# K210.net
KiCad netlist of a schematic drawn in Altium Designer
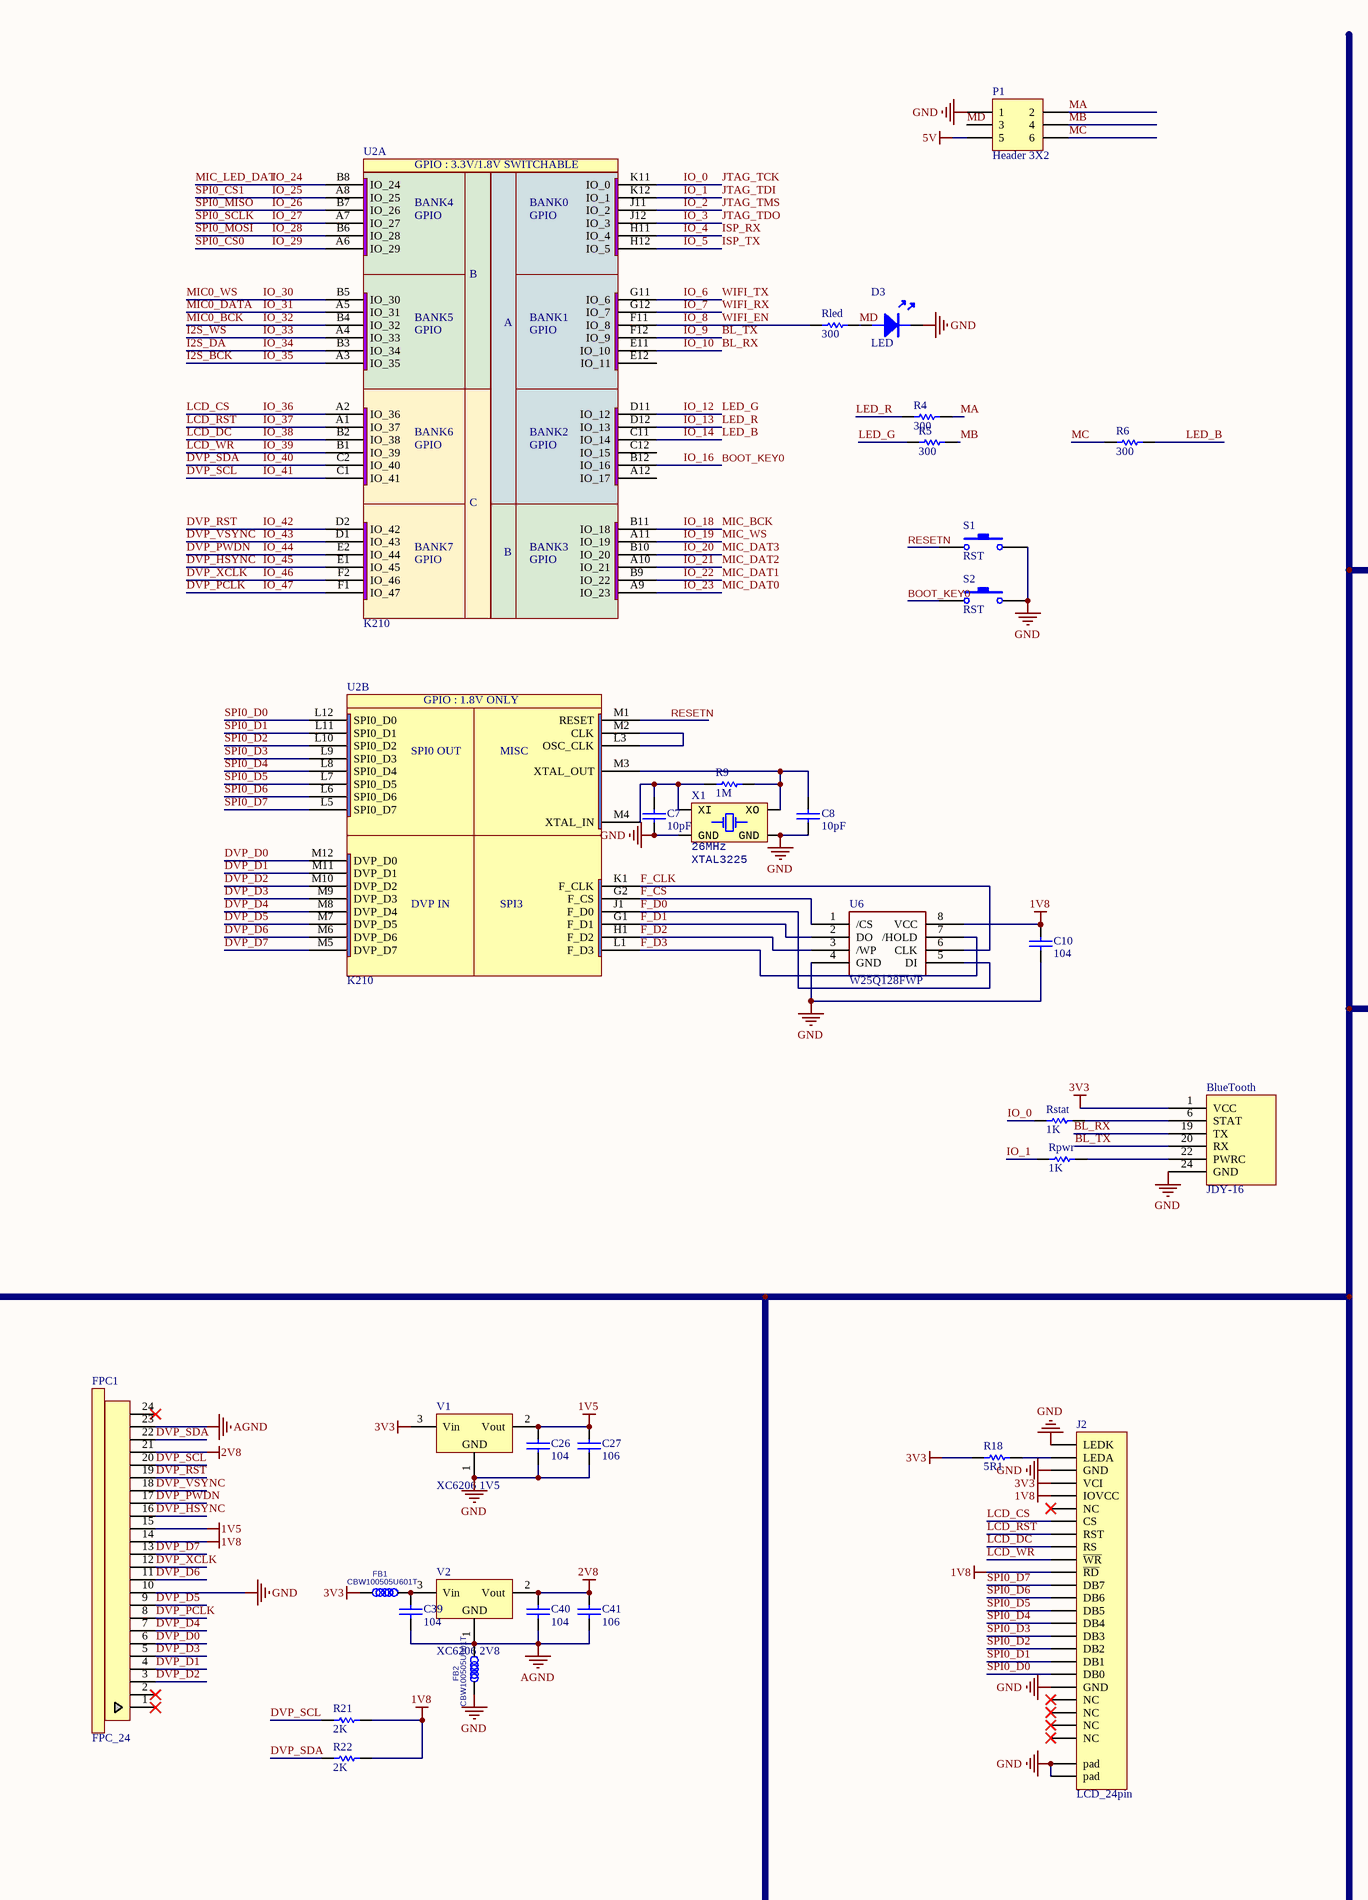
[diagram p0: K210.SchDoc, left]
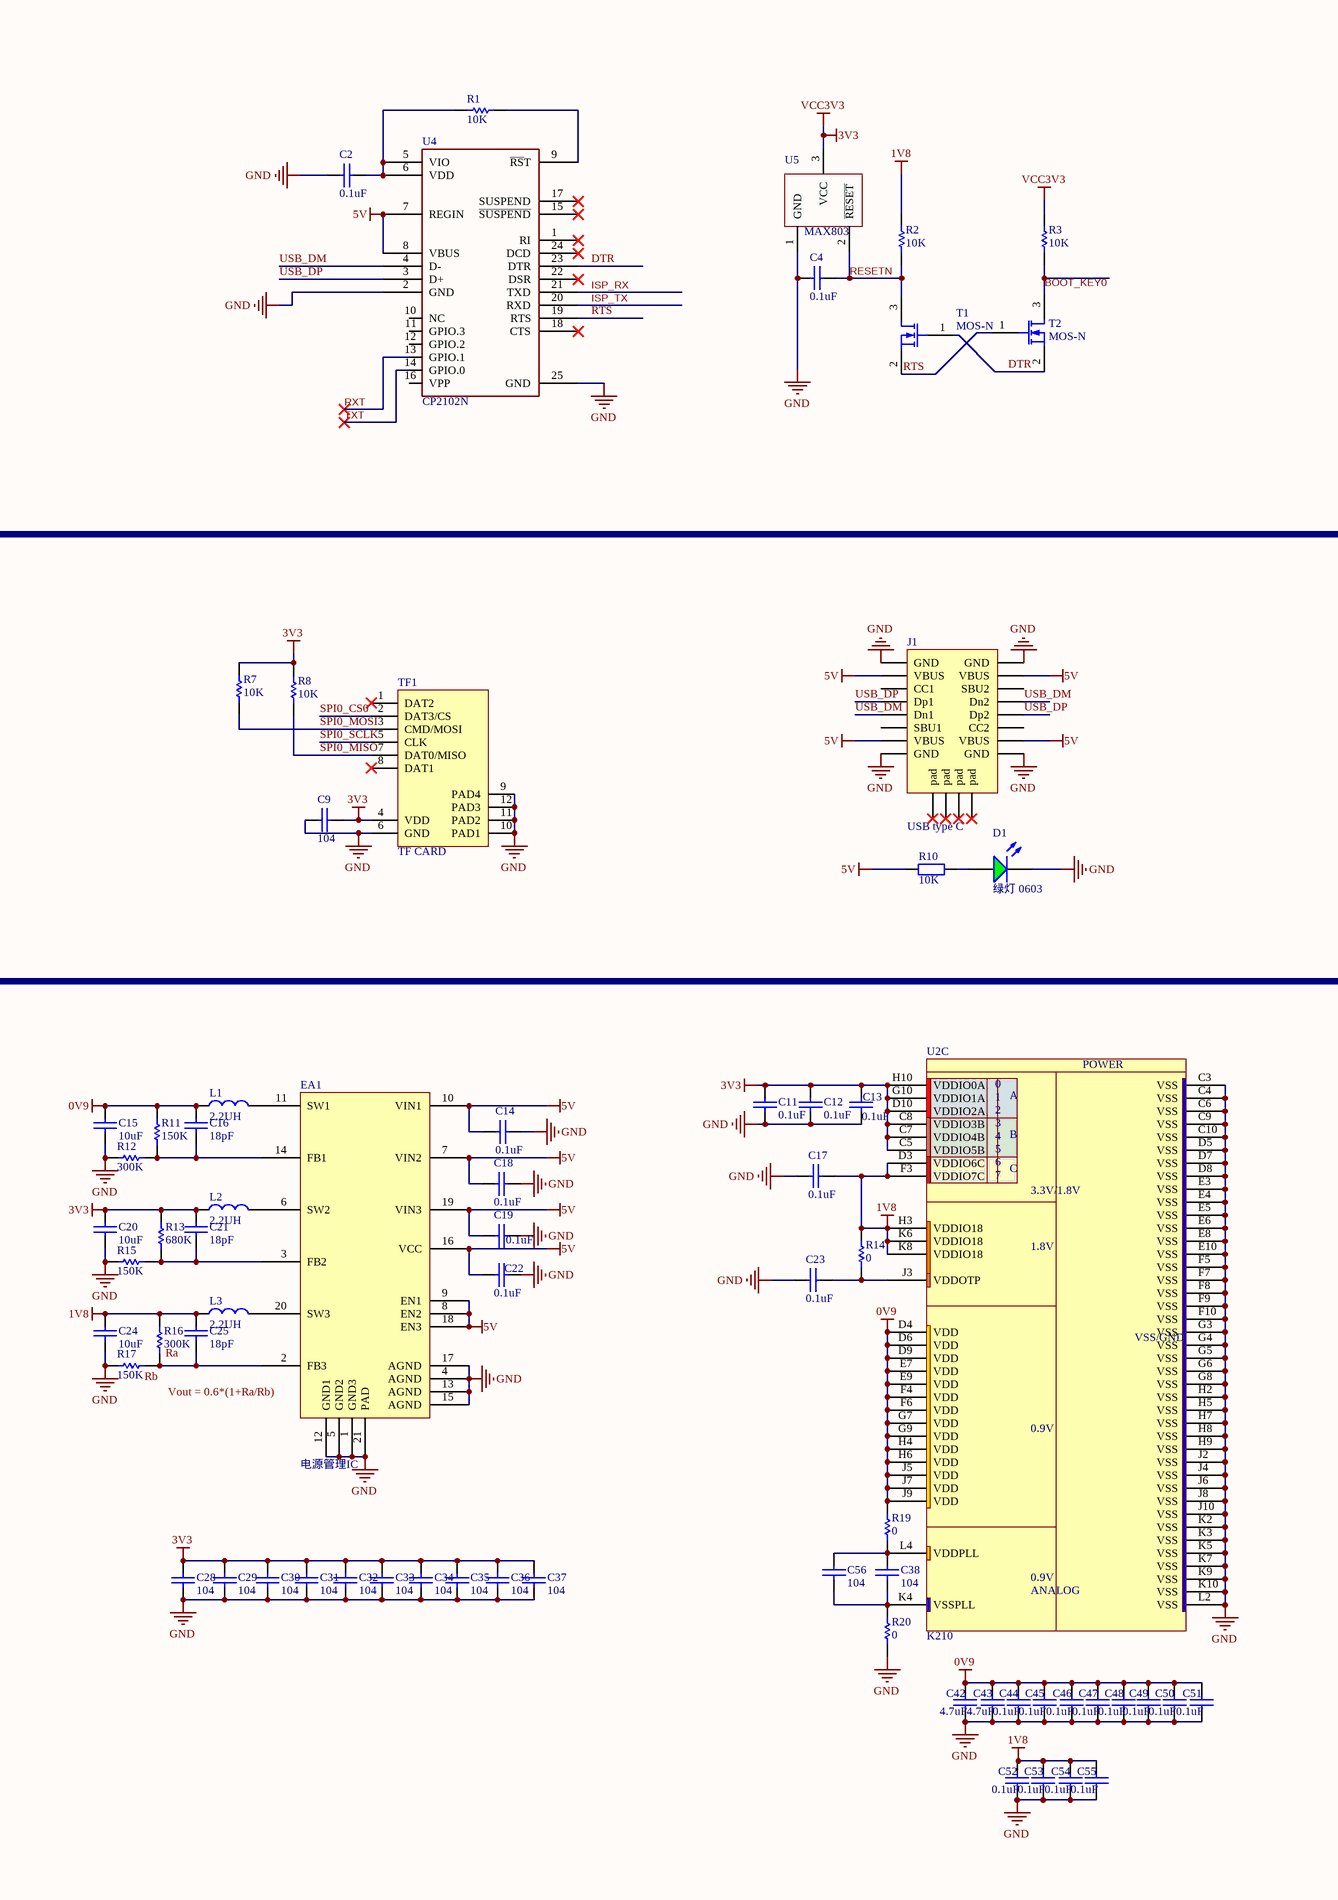
[diagram p1: K210.SchDoc, right]

(export (version "E")
  (design (tool "Eeschema 10.0.6"))
  (components
    (comp (ref "BlueTooth") (value "JDY-16") (footprint "JDY-16") (libsource (lib "未分类IC") (part "JDY-16")))
    (comp (ref "C2")
      (value "0.1uF")
      (footprint "0402C")
      (description "无极性电容")
      (libsource (lib "电容") (part "CAP"))
    )
    (comp (ref "C4")
      (value "0.1uF")
      (footprint "0402C")
      (description "无极性电容")
      (libsource (lib "电容") (part "CAP"))
    )
    (comp (ref "C7")
      (value "10pF")
      (footprint "0402C")
      (description "无极性电容")
      (libsource (lib "电容") (part "CAP"))
    )
    (comp (ref "C8")
      (value "10pF")
      (footprint "0402C")
      (description "无极性电容")
      (libsource (lib "电容") (part "CAP"))
    )
    (comp (ref "C9")
      (value "104")
      (footprint "0402C")
      (description "无极性电容")
      (libsource (lib "电容") (part "CAP"))
    )
    (comp (ref "C10")
      (value "104")
      (footprint "0402C")
      (description "无极性电容")
      (libsource (lib "电容") (part "CAP"))
    )
    (comp (ref "C11")
      (value "0.1uF")
      (footprint "0402C")
      (description "无极性电容")
      (libsource (lib "电容") (part "CAP"))
    )
    (comp (ref "C12")
      (value "0.1uF")
      (footprint "0402C")
      (description "无极性电容")
      (libsource (lib "电容") (part "CAP"))
    )
    (comp (ref "C13")
      (value "0.1uF")
      (footprint "0402C")
      (description "无极性电容")
      (libsource (lib "电容") (part "CAP"))
    )
    (comp (ref "C14")
      (value "0.1uF")
      (footprint "0402C")
      (description "无极性电容")
      (libsource (lib "电容") (part "CAP"))
    )
    (comp (ref "C15")
      (value "10uF")
      (footprint "0402C")
      (description "无极性电容")
      (libsource (lib "电容") (part "CAP"))
    )
    (comp (ref "C16")
      (value "18pF")
      (footprint "0402C")
      (description "无极性电容")
      (libsource (lib "电容") (part "CAP"))
    )
    (comp (ref "C17")
      (value "0.1uF")
      (footprint "0402C")
      (description "无极性电容")
      (libsource (lib "电容") (part "CAP"))
    )
    (comp (ref "C18")
      (value "0.1uF")
      (footprint "0402C")
      (description "无极性电容")
      (libsource (lib "电容") (part "CAP"))
    )
    (comp (ref "C19")
      (value "0.1uF")
      (footprint "0402C")
      (description "无极性电容")
      (libsource (lib "电容") (part "CAP"))
    )
    (comp (ref "C20")
      (value "10uF")
      (footprint "0402C")
      (description "无极性电容")
      (libsource (lib "电容") (part "CAP"))
    )
    (comp (ref "C21")
      (value "18pF")
      (footprint "0402C")
      (description "无极性电容")
      (libsource (lib "电容") (part "CAP"))
    )
    (comp (ref "C22")
      (value "0.1uF")
      (footprint "0402C")
      (description "无极性电容")
      (libsource (lib "电容") (part "CAP"))
    )
    (comp (ref "C23")
      (value "0.1uF")
      (footprint "0402C")
      (description "无极性电容")
      (libsource (lib "电容") (part "CAP"))
    )
    (comp (ref "C24")
      (value "10uF")
      (footprint "0402C")
      (description "无极性电容")
      (libsource (lib "电容") (part "CAP"))
    )
    (comp (ref "C25")
      (value "18pF")
      (footprint "0402C")
      (description "无极性电容")
      (libsource (lib "电容") (part "CAP"))
    )
    (comp (ref "C26")
      (value "104")
      (footprint "0402C")
      (description "无极性电容")
      (libsource (lib "电容") (part "CAP"))
    )
    (comp (ref "C27")
      (value "106")
      (footprint "0402C")
      (description "无极性电容")
      (libsource (lib "电容") (part "CAP"))
    )
    (comp (ref "C28")
      (value "104")
      (footprint "0402C")
      (description "无极性电容")
      (libsource (lib "电容") (part "CAP"))
    )
    (comp (ref "C29")
      (value "104")
      (footprint "0402C")
      (description "无极性电容")
      (libsource (lib "电容") (part "CAP"))
    )
    (comp (ref "C30")
      (value "104")
      (footprint "0402C")
      (description "无极性电容")
      (libsource (lib "电容") (part "CAP"))
    )
    (comp (ref "C31")
      (value "104")
      (footprint "0402C")
      (description "无极性电容")
      (libsource (lib "电容") (part "CAP"))
    )
    (comp (ref "C32")
      (value "104")
      (footprint "0402C")
      (description "无极性电容")
      (libsource (lib "电容") (part "CAP"))
    )
    (comp (ref "C33")
      (value "104")
      (footprint "0402C")
      (description "无极性电容")
      (libsource (lib "电容") (part "CAP"))
    )
    (comp (ref "C34")
      (value "104")
      (footprint "0402C")
      (description "无极性电容")
      (libsource (lib "电容") (part "CAP"))
    )
    (comp (ref "C35")
      (value "104")
      (footprint "0402C")
      (description "无极性电容")
      (libsource (lib "电容") (part "CAP"))
    )
    (comp (ref "C36")
      (value "104")
      (footprint "0402C")
      (description "无极性电容")
      (libsource (lib "电容") (part "CAP"))
    )
    (comp (ref "C37")
      (value "104")
      (footprint "0402C")
      (description "无极性电容")
      (libsource (lib "电容") (part "CAP"))
    )
    (comp (ref "C38")
      (value "104")
      (footprint "0402C")
      (description "无极性电容")
      (libsource (lib "电容") (part "CAP"))
    )
    (comp (ref "C39")
      (value "104")
      (footprint "0402C")
      (description "无极性电容")
      (libsource (lib "电容") (part "CAP"))
    )
    (comp (ref "C40")
      (value "104")
      (footprint "0402C")
      (description "无极性电容")
      (libsource (lib "电容") (part "CAP"))
    )
    (comp (ref "C41")
      (value "106")
      (footprint "0402C")
      (description "无极性电容")
      (libsource (lib "电容") (part "CAP"))
    )
    (comp (ref "C42")
      (value "4.7uF")
      (footprint "0402C")
      (description "无极性电容")
      (libsource (lib "电容") (part "CAP"))
    )
    (comp (ref "C43")
      (value "4.7uF")
      (footprint "0402C")
      (description "无极性电容")
      (libsource (lib "电容") (part "CAP"))
    )
    (comp (ref "C44")
      (value "0.1uF")
      (footprint "0402C")
      (description "无极性电容")
      (libsource (lib "电容") (part "CAP"))
    )
    (comp (ref "C45")
      (value "0.1uF")
      (footprint "0402C")
      (description "无极性电容")
      (libsource (lib "电容") (part "CAP"))
    )
    (comp (ref "C46")
      (value "0.1uF")
      (footprint "0402C")
      (description "无极性电容")
      (libsource (lib "电容") (part "CAP"))
    )
    (comp (ref "C47")
      (value "0.1uF")
      (footprint "0402C")
      (description "无极性电容")
      (libsource (lib "电容") (part "CAP"))
    )
    (comp (ref "C48")
      (value "0.1uF")
      (footprint "0402C")
      (description "无极性电容")
      (libsource (lib "电容") (part "CAP"))
    )
    (comp (ref "C49")
      (value "0.1uF")
      (footprint "0402C")
      (description "无极性电容")
      (libsource (lib "电容") (part "CAP"))
    )
    (comp (ref "C50")
      (value "0.1uF")
      (footprint "0402C")
      (description "无极性电容")
      (libsource (lib "电容") (part "CAP"))
    )
    (comp (ref "C51")
      (value "0.1uF")
      (footprint "0402C")
      (description "无极性电容")
      (libsource (lib "电容") (part "CAP"))
    )
    (comp (ref "C52")
      (value "0.1uF")
      (footprint "0402C")
      (description "无极性电容")
      (libsource (lib "电容") (part "CAP"))
    )
    (comp (ref "C53")
      (value "0.1uF")
      (footprint "0402C")
      (description "无极性电容")
      (libsource (lib "电容") (part "CAP"))
    )
    (comp (ref "C54")
      (value "0.1uF")
      (footprint "0402C")
      (description "无极性电容")
      (libsource (lib "电容") (part "CAP"))
    )
    (comp (ref "C55")
      (value "0.1uF")
      (footprint "0402C")
      (description "无极性电容")
      (libsource (lib "电容") (part "CAP"))
    )
    (comp (ref "C56")
      (value "104")
      (footprint "0402C")
      (description "无极性电容")
      (libsource (lib "电容") (part "CAP"))
    )
    (comp (ref "D1")
      (value "绿灯 0603")
      (footprint "0603_LED")
      (description "发光二极管")
      (libsource (lib "Miscellaneous Devices LC") (part "0603 绿灯"))
    )
    (comp (ref "D3") (value "LED") (footprint "LED-0603B") (libsource (lib "LED") (part "LED")))
    (comp (ref "EA1") (value "电源管理IC") (footprint "QFN20 3x3_M") (libsource (lib "XKZ") (part "EA3036")))
    (comp (ref "FB1") (value "CBW100505U601T") (footprint "0603_R") (libsource (lib "XKZ") (part "FB")))
    (comp (ref "FB2") (value "CBW100505U601T") (footprint "0603_R") (libsource (lib "XKZ") (part "FB")))
    (comp (ref "FPC1") (value "FPC_24") (footprint "FPC_24") (libsource (lib "XKZ") (part "FPC_24")))
    (comp (ref "J1")
      (value "USB type C")
      (footprint "USB Type-C-16Pin_A")
      (libsource (lib "XKZ") (part "USB_C"))
    )
    (comp (ref "J2") (value "LCD_24pin") (footprint "OV7740") (libsource (lib "XKZ") (part "LCD_24pin")))
    (comp (ref "L1")
      (value "2.2UH")
      (footprint "NR3015")
      (description "电感")
      (libsource (lib "XKZ") (part "L1"))
    )
    (comp (ref "L2")
      (value "2.2UH")
      (footprint "NR3015")
      (description "电感")
      (libsource (lib "XKZ") (part "L1"))
    )
    (comp (ref "L3")
      (value "2.2UH")
      (footprint "NR3015")
      (description "电感")
      (libsource (lib "XKZ") (part "L1"))
    )
    (comp (ref "P1")
      (value "Header 3X2")
      (footprint "HDR2X3")
      (description "Header, 3-Pin, Dual row")
      (fields (field (name "PUBLISHER") "Altium Limited"))
      (libsource (lib "Miscellaneous Connectors") (part "Header 3X2"))
    )
    (comp (ref "R1") (value "10K") (footprint "0402R") (libsource (lib "电阻") (part "RES")))
    (comp (ref "R2") (value "10K") (footprint "0402R") (libsource (lib "电阻") (part "RES")))
    (comp (ref "R3") (value "10K") (footprint "0402R") (libsource (lib "电阻") (part "RES")))
    (comp (ref "R4") (value "300") (footprint "0402R") (libsource (lib "电阻") (part "RES")))
    (comp (ref "R5") (value "300") (footprint "0402R") (libsource (lib "电阻") (part "RES")))
    (comp (ref "R6") (value "300") (footprint "0402R") (libsource (lib "电阻") (part "RES")))
    (comp (ref "R7") (value "10K") (footprint "0402R") (libsource (lib "电阻") (part "RES")))
    (comp (ref "R8") (value "10K") (footprint "0402R") (libsource (lib "电阻") (part "RES")))
    (comp (ref "R9") (value "1M") (footprint "0402R") (libsource (lib "电阻") (part "RES")))
    (comp (ref "R10")
      (value "10K")
      (footprint "0603_R")
      (description "Resistor")
      (fields (field (name "Comment") "Res2") (field (name "PUBLISHER") "Altium Limited"))
      (libsource (lib "XKZ") (part "Res2"))
    )
    (comp (ref "R11") (value "150K") (footprint "0402R") (libsource (lib "电阻") (part "RES")))
    (comp (ref "R12") (value "300K") (footprint "0402R") (libsource (lib "电阻") (part "RES")))
    (comp (ref "R13") (value "680K") (footprint "0402R") (libsource (lib "电阻") (part "RES")))
    (comp (ref "R14") (value "0") (footprint "0402R") (libsource (lib "电阻") (part "RES")))
    (comp (ref "R15") (value "150K") (footprint "0402R") (libsource (lib "电阻") (part "RES")))
    (comp (ref "R16") (value "300K") (footprint "0402R") (libsource (lib "电阻") (part "RES")))
    (comp (ref "R17") (value "150K") (footprint "0402R") (libsource (lib "电阻") (part "RES")))
    (comp (ref "R18") (value "5R1") (footprint "0402R") (libsource (lib "电阻") (part "RES")))
    (comp (ref "R19") (value "0") (footprint "0402R") (libsource (lib "电阻") (part "RES")))
    (comp (ref "R20") (value "0") (footprint "0402R") (libsource (lib "电阻") (part "RES")))
    (comp (ref "R21") (value "2K") (footprint "0402R") (libsource (lib "电阻") (part "RES")))
    (comp (ref "R22") (value "2K") (footprint "0402R") (libsource (lib "电阻") (part "RES")))
    (comp (ref "Rled") (value "300") (footprint "0402R") (libsource (lib "电阻") (part "RES")))
    (comp (ref "Rpwr") (value "1K") (footprint "0402R") (libsource (lib "电阻") (part "RES")))
    (comp (ref "Rstat") (value "1K") (footprint "0402R") (libsource (lib "电阻") (part "RES")))
    (comp (ref "S1")
      (value "RST")
      (footprint "KEY_1")
      (description "Switch")
      (fields (field (name "PUBLISHER") "Altium Limited"))
      (libsource (lib "自创 (1)") (part "SW-PB"))
    )
    (comp (ref "S2")
      (value "RST")
      (footprint "KEY_1")
      (description "Switch")
      (fields (field (name "PUBLISHER") "Altium Limited"))
      (libsource (lib "自创 (1)") (part "SW-PB"))
    )
    (comp (ref "T1") (value "MOS-N") (footprint "SOT23-3N") (libsource (lib "LIB_MANGO") (part "MOS-N")))
    (comp (ref "T2") (value "MOS-N") (footprint "SOT23-3N") (libsource (lib "LIB_MANGO") (part "MOS-N")))
    (comp (ref "TF1") (value "TF CARD") (footprint "TF卡座") (libsource (lib "XKZ") (part "SD_Card_flip")))
    (comp (ref "U2")
      (value "K210")
      (footprint "BGA144C65P12X12_800X800X95")
      (description "Canaan Kendryte K210 AI SoC")
      (libsource (lib "Vowstar_MCU") (part "K210"))
    )
    (comp (ref "U4")
      (value "CP2102N")
      (footprint "QFN24 4x4_N")
      (libsource (lib "LIB_MANGO") (part "CP2104"))
    )
    (comp (ref "U5") (value "MAX803") (footprint "SOT23-3N") (libsource (lib "LIB_MANGO") (part "MAX809")))
    (comp (ref "U6")
      (value "W25Q128FWP")
      (footprint "WSON8")
      (libsource (lib "LIB_MANGO") (part "SPIFLASH_SOP8W"))
    )
    (comp (ref "V1")
      (value "XC6206 1V5")
      (footprint "SOT23-3N")
      (description "低压差线性稳压芯片")
      (fields (field (name "版权归属") "源创客"))
      (libsource (lib "XKZ") (part "XC6206P332MR"))
    )
    (comp (ref "V2")
      (value "XC6206 2V8")
      (footprint "SOT23-3N")
      (description "低压差线性稳压芯片")
      (fields (field (name "版权归属") "源创客"))
      (libsource (lib "XKZ") (part "XC6206P332MR"))
    )
    (comp (ref "X1")
      (value "26MHz")
      (footprint "XT_3225_4")
      (description "Crystal Oscillator")
      (fields (field (name "TYPE") "XTAL3225"))
      (libsource (lib "XKZ") (part "XTAL_3225_4P"))
    )
  )
  (nets
    (net (code "1") (name "/BL_RX") (class "Default")
      (node (ref "BlueTooth") (pin "19") (pinfunction "TX_19") (pintype "passive"))
      (node (ref "U2") (pin "E11") (pinfunction "IO_10_E11") (pintype "passive"))
    )
    (net (code "2") (name "/BL_TX") (class "Default")
      (node (ref "BlueTooth") (pin "20") (pinfunction "RX_20") (pintype "passive"))
      (node (ref "U2") (pin "F12") (pinfunction "IO_9_F12") (pintype "passive"))
    )
    (net (code "3") (name "/BOOT_KEY0") (class "Default")
      (node (ref "R3") (pin "1") (pinfunction "1_1") (pintype "passive"))
      (node (ref "S2") (pin "1") (pinfunction "1_1") (pintype "passive"))
      (node (ref "T2") (pin "3") (pinfunction "3_3") (pintype "passive"))
      (node (ref "U2") (pin "B12") (pinfunction "IO_16_B12") (pintype "passive"))
    )
    (net (code "4") (name "/DTR") (class "Default")
      (node (ref "T1") (pin "1") (pinfunction "1_1") (pintype "passive"))
      (node (ref "T2") (pin "2") (pinfunction "2_2") (pintype "passive"))
      (node (ref "U4") (pin "23") (pinfunction "DTR_23") (pintype "passive"))
    )
    (net (code "5") (name "/DVP_D0") (class "Default")
      (node (ref "FPC1") (pin "6") (pinfunction "6_6") (pintype "passive"))
      (node (ref "U2") (pin "M12") (pinfunction "DVP_D0_M12") (pintype "passive"))
    )
    (net (code "6") (name "/DVP_D1") (class "Default")
      (node (ref "FPC1") (pin "4") (pinfunction "4_4") (pintype "passive"))
      (node (ref "U2") (pin "M11") (pinfunction "DVP_D1_M11") (pintype "passive"))
    )
    (net (code "7") (name "/DVP_D2") (class "Default")
      (node (ref "FPC1") (pin "3") (pinfunction "3_3") (pintype "passive"))
      (node (ref "U2") (pin "M10") (pinfunction "DVP_D2_M10") (pintype "passive"))
    )
    (net (code "8") (name "/DVP_D3") (class "Default")
      (node (ref "FPC1") (pin "5") (pinfunction "5_5") (pintype "passive"))
      (node (ref "U2") (pin "M9") (pinfunction "DVP_D3_M9") (pintype "passive"))
    )
    (net (code "9") (name "/DVP_D4") (class "Default")
      (node (ref "FPC1") (pin "7") (pinfunction "7_7") (pintype "passive"))
      (node (ref "U2") (pin "M8") (pinfunction "DVP_D4_M8") (pintype "passive"))
    )
    (net (code "10") (name "/DVP_D5") (class "Default")
      (node (ref "FPC1") (pin "9") (pinfunction "9_9") (pintype "passive"))
      (node (ref "U2") (pin "M7") (pinfunction "DVP_D5_M7") (pintype "passive"))
    )
    (net (code "11") (name "/DVP_D6") (class "Default")
      (node (ref "FPC1") (pin "11") (pinfunction "11_11") (pintype "passive"))
      (node (ref "U2") (pin "M6") (pinfunction "DVP_D6_M6") (pintype "passive"))
    )
    (net (code "12") (name "/DVP_D7") (class "Default")
      (node (ref "FPC1") (pin "13") (pinfunction "13_13") (pintype "passive"))
      (node (ref "U2") (pin "M5") (pinfunction "DVP_D7_M5") (pintype "passive"))
    )
    (net (code "13") (name "/DVP_HSYNC") (class "Default")
      (node (ref "FPC1") (pin "16") (pinfunction "16_16") (pintype "passive"))
      (node (ref "U2") (pin "E1") (pinfunction "IO_45_E1") (pintype "passive"))
    )
    (net (code "14") (name "/DVP_PCLK") (class "Default")
      (node (ref "FPC1") (pin "8") (pinfunction "8_8") (pintype "passive"))
      (node (ref "U2") (pin "F1") (pinfunction "IO_47_F1") (pintype "passive"))
    )
    (net (code "15") (name "/DVP_PWDN") (class "Default")
      (node (ref "FPC1") (pin "17") (pinfunction "17_17") (pintype "passive"))
      (node (ref "U2") (pin "E2") (pinfunction "IO_44_E2") (pintype "passive"))
    )
    (net (code "16") (name "/DVP_RST") (class "Default")
      (node (ref "FPC1") (pin "19") (pinfunction "19_19") (pintype "passive"))
      (node (ref "U2") (pin "D2") (pinfunction "IO_42_D2") (pintype "passive"))
    )
    (net (code "17") (name "/DVP_SCL") (class "Default")
      (node (ref "FPC1") (pin "20") (pinfunction "20_20") (pintype "passive"))
      (node (ref "R21") (pin "2") (pinfunction "2_2") (pintype "passive"))
      (node (ref "U2") (pin "C1") (pinfunction "IO_41_C1") (pintype "passive"))
    )
    (net (code "18") (name "/DVP_SDA") (class "Default")
      (node (ref "FPC1") (pin "22") (pinfunction "22_22") (pintype "passive"))
      (node (ref "R22") (pin "2") (pinfunction "2_2") (pintype "passive"))
      (node (ref "U2") (pin "C2") (pinfunction "IO_40_C2") (pintype "passive"))
    )
    (net (code "19") (name "/DVP_VSYNC") (class "Default")
      (node (ref "FPC1") (pin "18") (pinfunction "18_18") (pintype "passive"))
      (node (ref "U2") (pin "D1") (pinfunction "IO_43_D1") (pintype "passive"))
    )
    (net (code "20") (name "/DVP_XCLK") (class "Default")
      (node (ref "FPC1") (pin "12") (pinfunction "12_12") (pintype "passive"))
      (node (ref "U2") (pin "F2") (pinfunction "IO_46_F2") (pintype "passive"))
    )
    (net (code "21") (name "/F_CLK") (class "Default")
      (node (ref "U2") (pin "K1") (pinfunction "F_CLK_K1") (pintype "passive"))
      (node (ref "U6") (pin "6") (pinfunction "CLK_6") (pintype "passive"))
    )
    (net (code "22") (name "/F_CS") (class "Default")
      (node (ref "U2") (pin "G2") (pinfunction "F_CS_G2") (pintype "passive"))
      (node (ref "U6") (pin "1") (pinfunction "/CS_1") (pintype "passive"))
    )
    (net (code "23") (name "/F_D0") (class "Default")
      (node (ref "U2") (pin "J1") (pinfunction "F_D0_J1") (pintype "passive"))
      (node (ref "U6") (pin "5") (pinfunction "DI_5") (pintype "passive"))
    )
    (net (code "24") (name "/F_D1") (class "Default")
      (node (ref "U2") (pin "G1") (pinfunction "F_D1_G1") (pintype "passive"))
      (node (ref "U6") (pin "2") (pinfunction "DO_2") (pintype "passive"))
    )
    (net (code "25") (name "/F_D2") (class "Default")
      (node (ref "U2") (pin "H1") (pinfunction "F_D2_H1") (pintype "passive"))
      (node (ref "U6") (pin "3") (pinfunction "/WP_3") (pintype "passive"))
    )
    (net (code "26") (name "/F_D3") (class "Default")
      (node (ref "U2") (pin "L1") (pinfunction "F_D3_L1") (pintype "passive"))
      (node (ref "U6") (pin "7") (pinfunction "/HOLD_7") (pintype "passive"))
    )
    (net (code "27") (name "/I2S_BCK") (class "Default")
      (node (ref "U2") (pin "A3") (pinfunction "IO_35_A3") (pintype "passive"))
    )
    (net (code "28") (name "/I2S_DA") (class "Default")
      (node (ref "U2") (pin "B3") (pinfunction "IO_34_B3") (pintype "passive"))
    )
    (net (code "29") (name "/I2S_WS") (class "Default")
      (node (ref "U2") (pin "A4") (pinfunction "IO_33_A4") (pintype "passive"))
    )
    (net (code "30") (name "/IO_0") (class "Default")
      (node (ref "Rstat") (pin "2") (pinfunction "2_2") (pintype "passive"))
      (node (ref "U2") (pin "K11") (pinfunction "IO_0_K11") (pintype "passive"))
    )
    (net (code "31") (name "/IO_1") (class "Default")
      (node (ref "Rpwr") (pin "2") (pinfunction "2_2") (pintype "passive"))
      (node (ref "U2") (pin "K12") (pinfunction "IO_1_K12") (pintype "passive"))
    )
    (net (code "32") (name "/IO_2") (class "Default")
      (node (ref "U2") (pin "J11") (pinfunction "IO_2_J11") (pintype "passive"))
    )
    (net (code "33") (name "/IO_3") (class "Default")
      (node (ref "U2") (pin "J12") (pinfunction "IO_3_J12") (pintype "passive"))
    )
    (net (code "34") (name "/IO_4") (class "Default")
      (node (ref "U2") (pin "H11") (pinfunction "IO_4_H11") (pintype "passive"))
      (node (ref "U4") (pin "21") (pinfunction "TXD_21") (pintype "passive"))
    )
    (net (code "35") (name "/IO_5") (class "Default")
      (node (ref "U2") (pin "H12") (pinfunction "IO_5_H12") (pintype "passive"))
      (node (ref "U4") (pin "20") (pinfunction "RXD_20") (pintype "passive"))
    )
    (net (code "36") (name "/IO_6") (class "Default")
      (node (ref "U2") (pin "G11") (pinfunction "IO_6_G11") (pintype "passive"))
    )
    (net (code "37") (name "/IO_7") (class "Default")
      (node (ref "U2") (pin "G12") (pinfunction "IO_7_G12") (pintype "passive"))
    )
    (net (code "38") (name "/IO_8") (class "Default")
      (node (ref "Rled") (pin "2") (pinfunction "2_2") (pintype "passive"))
      (node (ref "U2") (pin "F11") (pinfunction "IO_8_F11") (pintype "passive"))
    )
    (net (code "39") (name "/IO_12") (class "Default")
      (node (ref "R5") (pin "2") (pinfunction "2_2") (pintype "passive"))
      (node (ref "U2") (pin "D11") (pinfunction "IO_12_D11") (pintype "passive"))
    )
    (net (code "40") (name "/IO_13") (class "Default")
      (node (ref "R4") (pin "2") (pinfunction "2_2") (pintype "passive"))
      (node (ref "U2") (pin "D12") (pinfunction "IO_13_D12") (pintype "passive"))
    )
    (net (code "41") (name "/IO_14") (class "Default")
      (node (ref "R6") (pin "1") (pinfunction "1_1") (pintype "passive"))
      (node (ref "U2") (pin "C11") (pinfunction "IO_14_C11") (pintype "passive"))
    )
    (net (code "42") (name "/IO_18") (class "Default")
      (node (ref "U2") (pin "B11") (pinfunction "IO_18_B11") (pintype "passive"))
    )
    (net (code "43") (name "/IO_19") (class "Default")
      (node (ref "U2") (pin "A11") (pinfunction "IO_19_A11") (pintype "passive"))
    )
    (net (code "44") (name "/IO_20") (class "Default")
      (node (ref "U2") (pin "B10") (pinfunction "IO_20_B10") (pintype "passive"))
    )
    (net (code "45") (name "/IO_21") (class "Default")
      (node (ref "U2") (pin "A10") (pinfunction "IO_21_A10") (pintype "passive"))
    )
    (net (code "46") (name "/IO_22") (class "Default")
      (node (ref "U2") (pin "B9") (pinfunction "IO_22_B9") (pintype "passive"))
    )
    (net (code "47") (name "/IO_23") (class "Default")
      (node (ref "U2") (pin "A9") (pinfunction "IO_23_A9") (pintype "passive"))
    )
    (net (code "48") (name "/IO_24") (class "Default")
      (node (ref "U2") (pin "B8") (pinfunction "IO_24_B8") (pintype "passive"))
    )
    (net (code "49") (name "/IO_25") (class "Default")
      (node (ref "U2") (pin "A8") (pinfunction "IO_25_A8") (pintype "passive"))
    )
    (net (code "50") (name "/IO_26") (class "Default")
      (node (ref "R8") (pin "1") (pinfunction "1_1") (pintype "passive"))
      (node (ref "TF1") (pin "7") (pinfunction "DAT0/MISO_7") (pintype "passive"))
      (node (ref "U2") (pin "B7") (pinfunction "IO_26_B7") (pintype "passive"))
    )
    (net (code "51") (name "/IO_27") (class "Default")
      (node (ref "TF1") (pin "5") (pinfunction "CLK_5") (pintype "passive"))
      (node (ref "U2") (pin "A7") (pinfunction "IO_27_A7") (pintype "passive"))
    )
    (net (code "52") (name "/IO_28") (class "Default")
      (node (ref "R7") (pin "1") (pinfunction "1_1") (pintype "passive"))
      (node (ref "TF1") (pin "3") (pinfunction "CMD/MOSI_3") (pintype "passive"))
      (node (ref "U2") (pin "B6") (pinfunction "IO_28_B6") (pintype "passive"))
    )
    (net (code "53") (name "/IO_29") (class "Default")
      (node (ref "TF1") (pin "2") (pinfunction "DAT3/CS_2") (pintype "passive"))
      (node (ref "U2") (pin "A6") (pinfunction "IO_29_A6") (pintype "passive"))
    )
    (net (code "54") (name "/IO_30") (class "Default")
      (node (ref "U2") (pin "B5") (pinfunction "IO_30_B5") (pintype "passive"))
    )
    (net (code "55") (name "/IO_31") (class "Default")
      (node (ref "U2") (pin "A5") (pinfunction "IO_31_A5") (pintype "passive"))
    )
    (net (code "56") (name "/IO_32") (class "Default")
      (node (ref "U2") (pin "B4") (pinfunction "IO_32_B4") (pintype "passive"))
    )
    (net (code "57") (name "/IO_36") (class "Default")
      (node (ref "J2") (pin "7") (pinfunction "CS_7") (pintype "passive"))
      (node (ref "U2") (pin "A2") (pinfunction "IO_36_A2") (pintype "passive"))
    )
    (net (code "58") (name "/IO_37") (class "Default")
      (node (ref "J2") (pin "8") (pinfunction "RST_8") (pintype "passive"))
      (node (ref "U2") (pin "A1") (pinfunction "IO_37_A1") (pintype "passive"))
    )
    (net (code "59") (name "/IO_38") (class "Default")
      (node (ref "J2") (pin "9") (pinfunction "RS_9") (pintype "passive"))
      (node (ref "U2") (pin "B2") (pinfunction "IO_38_B2") (pintype "passive"))
    )
    (net (code "60") (name "/IO_39") (class "Default")
      (node (ref "J2") (pin "10") (pinfunction "~{WR}_10") (pintype "passive"))
      (node (ref "U2") (pin "B1") (pinfunction "IO_39_B1") (pintype "passive"))
    )
    (net (code "61") (name "/MA") (class "Default")
      (node (ref "P1") (pin "2") (pinfunction "2_2") (pintype "passive"))
      (node (ref "R4") (pin "1") (pinfunction "1_1") (pintype "passive"))
    )
    (net (code "62") (name "/MB") (class "Default")
      (node (ref "P1") (pin "4") (pinfunction "4_4") (pintype "passive"))
      (node (ref "R5") (pin "1") (pinfunction "1_1") (pintype "passive"))
    )
    (net (code "63") (name "/MC") (class "Default")
      (node (ref "P1") (pin "6") (pinfunction "6_6") (pintype "passive"))
      (node (ref "R6") (pin "2") (pinfunction "2_2") (pintype "passive"))
    )
    (net (code "64") (name "/MD") (class "Default")
      (node (ref "D3") (pin "A") (pinfunction "A_A") (pintype "passive"))
      (node (ref "P1") (pin "3") (pinfunction "3_3") (pintype "passive"))
      (node (ref "Rled") (pin "1") (pinfunction "1_1") (pintype "passive"))
    )
    (net (code "65") (name "/RESETN") (class "Default")
      (node (ref "C4") (pin "2") (pinfunction "2_2") (pintype "passive"))
      (node (ref "R2") (pin "1") (pinfunction "1_1") (pintype "passive"))
      (node (ref "S1") (pin "1") (pinfunction "1_1") (pintype "passive"))
      (node (ref "T1") (pin "3") (pinfunction "3_3") (pintype "passive"))
      (node (ref "U2") (pin "M1") (pinfunction "RESET_M1") (pintype "passive"))
      (node (ref "U5") (pin "2") (pinfunction "~{RESET}_2") (pintype "passive"))
    )
    (net (code "66") (name "/RTS") (class "Default")
      (node (ref "T1") (pin "2") (pinfunction "2_2") (pintype "passive"))
      (node (ref "T2") (pin "1") (pinfunction "1_1") (pintype "passive"))
      (node (ref "U4") (pin "19") (pinfunction "RTS_19") (pintype "passive"))
    )
    (net (code "67") (name "/RXT") (class "Default")
      (node (ref "U4") (pin "13") (pinfunction "GPIO.1_13") (pintype "passive+no_connect"))
    )
    (net (code "70") (name "/SPI0_D0") (class "Default")
      (node (ref "J2") (pin "19") (pinfunction "DB0_19") (pintype "passive"))
      (node (ref "U2") (pin "L12") (pinfunction "SPI0_D0_L12") (pintype "passive"))
    )
    (net (code "71") (name "/SPI0_D1") (class "Default")
      (node (ref "J2") (pin "18") (pinfunction "DB1_18") (pintype "passive"))
      (node (ref "U2") (pin "L11") (pinfunction "SPI0_D1_L11") (pintype "passive"))
    )
    (net (code "72") (name "/SPI0_D2") (class "Default")
      (node (ref "J2") (pin "17") (pinfunction "DB2_17") (pintype "passive"))
      (node (ref "U2") (pin "L10") (pinfunction "SPI0_D2_L10") (pintype "passive"))
    )
    (net (code "73") (name "/SPI0_D3") (class "Default")
      (node (ref "J2") (pin "16") (pinfunction "DB3_16") (pintype "passive"))
      (node (ref "U2") (pin "L9") (pinfunction "SPI0_D3_L9") (pintype "passive"))
    )
    (net (code "74") (name "/SPI0_D4") (class "Default")
      (node (ref "J2") (pin "15") (pinfunction "DB4_15") (pintype "passive"))
      (node (ref "U2") (pin "L8") (pinfunction "SPI0_D4_L8") (pintype "passive"))
    )
    (net (code "75") (name "/SPI0_D5") (class "Default")
      (node (ref "J2") (pin "14") (pinfunction "DB5_14") (pintype "passive"))
      (node (ref "U2") (pin "L7") (pinfunction "SPI0_D5_L7") (pintype "passive"))
    )
    (net (code "76") (name "/SPI0_D6") (class "Default")
      (node (ref "J2") (pin "13") (pinfunction "DB6_13") (pintype "passive"))
      (node (ref "U2") (pin "L6") (pinfunction "SPI0_D6_L6") (pintype "passive"))
    )
    (net (code "77") (name "/SPI0_D7") (class "Default")
      (node (ref "J2") (pin "12") (pinfunction "DB7_12") (pintype "passive"))
      (node (ref "U2") (pin "L5") (pinfunction "SPI0_D7_L5") (pintype "passive"))
    )
    (net (code "78") (name "/TXT") (class "Default")
      (node (ref "U4") (pin "14") (pinfunction "GPIO.0_14") (pintype "passive+no_connect"))
    )
    (net (code "79") (name "/USB_DM") (class "Default")
      (node (ref "J1") (pin "A7") (pinfunction "Dn1_A7") (pintype "passive"))
      (node (ref "J1") (pin "B7") (pinfunction "Dn2_B7") (pintype "passive"))
      (node (ref "U4") (pin "4") (pinfunction "D-_4") (pintype "passive"))
    )
    (net (code "80") (name "/USB_DP") (class "Default")
      (node (ref "J1") (pin "A6") (pinfunction "Dp1_A6") (pintype "passive"))
      (node (ref "J1") (pin "B6") (pinfunction "Dp2_B6") (pintype "passive"))
      (node (ref "U4") (pin "3") (pinfunction "D+_3") (pintype "passive"))
    )
    (net (code "82") (name "0V9") (class "Default")
      (node (ref "C15") (pin "1") (pinfunction "1_1") (pintype "passive"))
      (node (ref "C16") (pin "1") (pinfunction "1_1") (pintype "passive"))
      (node (ref "C42") (pin "2") (pinfunction "2_2") (pintype "passive"))
      (node (ref "C43") (pin "2") (pinfunction "2_2") (pintype "passive"))
      (node (ref "C44") (pin "2") (pinfunction "2_2") (pintype "passive"))
      (node (ref "C45") (pin "2") (pinfunction "2_2") (pintype "passive"))
      (node (ref "C46") (pin "2") (pinfunction "2_2") (pintype "passive"))
      (node (ref "C47") (pin "2") (pinfunction "2_2") (pintype "passive"))
      (node (ref "C48") (pin "2") (pinfunction "2_2") (pintype "passive"))
      (node (ref "C49") (pin "2") (pinfunction "2_2") (pintype "passive"))
      (node (ref "C50") (pin "2") (pinfunction "2_2") (pintype "passive"))
      (node (ref "C51") (pin "2") (pinfunction "2_2") (pintype "passive"))
      (node (ref "L1") (pin "2") (pinfunction "2_2") (pintype "passive"))
      (node (ref "R11") (pin "2") (pinfunction "2_2") (pintype "passive"))
      (node (ref "R19") (pin "2") (pinfunction "2_2") (pintype "passive"))
      (node (ref "U2") (pin "D4") (pinfunction "VDD_D4") (pintype "power_in"))
      (node (ref "U2") (pin "D6") (pinfunction "VDD_D6") (pintype "power_in"))
      (node (ref "U2") (pin "D9") (pinfunction "VDD_D9") (pintype "power_in"))
      (node (ref "U2") (pin "E7") (pinfunction "VDD_E7") (pintype "power_in"))
      (node (ref "U2") (pin "E9") (pinfunction "VDD_E9") (pintype "power_in"))
      (node (ref "U2") (pin "F4") (pinfunction "VDD_F4") (pintype "power_in"))
      (node (ref "U2") (pin "F6") (pinfunction "VDD_F6") (pintype "power_in"))
      (node (ref "U2") (pin "G7") (pinfunction "VDD_G7") (pintype "power_in"))
      (node (ref "U2") (pin "G9") (pinfunction "VDD_G9") (pintype "power_in"))
      (node (ref "U2") (pin "H4") (pinfunction "VDD_H4") (pintype "power_in"))
      (node (ref "U2") (pin "H6") (pinfunction "VDD_H6") (pintype "power_in"))
      (node (ref "U2") (pin "J5") (pinfunction "VDD_J5") (pintype "power_in"))
      (node (ref "U2") (pin "J7") (pinfunction "VDD_J7") (pintype "power_in"))
      (node (ref "U2") (pin "J9") (pinfunction "VDD_J9") (pintype "power_in"))
    )
    (net (code "83") (name "1V5") (class "Default")
      (node (ref "C26") (pin "2") (pinfunction "2_2") (pintype "passive"))
      (node (ref "C27") (pin "2") (pinfunction "2_2") (pintype "passive"))
      (node (ref "FPC1") (pin "15") (pinfunction "15_15") (pintype "passive"))
      (node (ref "V1") (pin "2") (pinfunction "Vout_2") (pintype "passive"))
    )
    (net (code "84") (name "1V8") (class "Default")
      (node (ref "C10") (pin "2") (pinfunction "2_2") (pintype "passive"))
      (node (ref "C17") (pin "1") (pinfunction "1_1") (pintype "passive"))
      (node (ref "C24") (pin "1") (pinfunction "1_1") (pintype "passive"))
      (node (ref "C25") (pin "1") (pinfunction "1_1") (pintype "passive"))
      (node (ref "C52") (pin "2") (pinfunction "2_2") (pintype "passive"))
      (node (ref "C53") (pin "2") (pinfunction "2_2") (pintype "passive"))
      (node (ref "C54") (pin "2") (pinfunction "2_2") (pintype "passive"))
      (node (ref "C55") (pin "2") (pinfunction "2_2") (pintype "passive"))
      (node (ref "FPC1") (pin "14") (pinfunction "14_14") (pintype "passive"))
      (node (ref "J2") (pin "11") (pinfunction "~{RD}_11") (pintype "passive"))
      (node (ref "J2") (pin "5") (pinfunction "IOVCC_5") (pintype "passive"))
      (node (ref "L3") (pin "2") (pinfunction "2_2") (pintype "passive"))
      (node (ref "R14") (pin "2") (pinfunction "2_2") (pintype "passive"))
      (node (ref "R16") (pin "2") (pinfunction "2_2") (pintype "passive"))
      (node (ref "R2") (pin "2") (pinfunction "2_2") (pintype "passive"))
      (node (ref "R21") (pin "1") (pinfunction "1_1") (pintype "passive"))
      (node (ref "R22") (pin "1") (pinfunction "1_1") (pintype "passive"))
      (node (ref "U2") (pin "D3") (pinfunction "VDDIO6C_D3") (pintype "power_in"))
      (node (ref "U2") (pin "F3") (pinfunction "VDDIO7C_F3") (pintype "power_in"))
      (node (ref "U2") (pin "H3") (pinfunction "VDDIO18_H3") (pintype "power_in"))
      (node (ref "U2") (pin "K6") (pinfunction "VDDIO18_K6") (pintype "power_in"))
      (node (ref "U2") (pin "K8") (pinfunction "VDDIO18_K8") (pintype "power_in"))
      (node (ref "U6") (pin "8") (pinfunction "VCC_8") (pintype "passive"))
    )
    (net (code "85") (name "2V8") (class "Default")
      (node (ref "C40") (pin "2") (pinfunction "2_2") (pintype "passive"))
      (node (ref "C41") (pin "2") (pinfunction "2_2") (pintype "passive"))
      (node (ref "FPC1") (pin "21") (pinfunction "21_21") (pintype "passive"))
      (node (ref "V2") (pin "2") (pinfunction "Vout_2") (pintype "passive"))
    )
    (net (code "86") (name "3V3") (class "Default")
      (node (ref "BlueTooth") (pin "1") (pinfunction "VCC_1") (pintype "passive"))
      (node (ref "C11") (pin "1") (pinfunction "1_1") (pintype "passive"))
      (node (ref "C12") (pin "1") (pinfunction "1_1") (pintype "passive"))
      (node (ref "C13") (pin "1") (pinfunction "1_1") (pintype "passive"))
      (node (ref "C20") (pin "1") (pinfunction "1_1") (pintype "passive"))
      (node (ref "C21") (pin "1") (pinfunction "1_1") (pintype "passive"))
      (node (ref "C28") (pin "2") (pinfunction "2_2") (pintype "passive"))
      (node (ref "C29") (pin "2") (pinfunction "2_2") (pintype "passive"))
      (node (ref "C30") (pin "2") (pinfunction "2_2") (pintype "passive"))
      (node (ref "C31") (pin "2") (pinfunction "2_2") (pintype "passive"))
      (node (ref "C32") (pin "2") (pinfunction "2_2") (pintype "passive"))
      (node (ref "C33") (pin "2") (pinfunction "2_2") (pintype "passive"))
      (node (ref "C34") (pin "2") (pinfunction "2_2") (pintype "passive"))
      (node (ref "C35") (pin "2") (pinfunction "2_2") (pintype "passive"))
      (node (ref "C36") (pin "2") (pinfunction "2_2") (pintype "passive"))
      (node (ref "C37") (pin "2") (pinfunction "2_2") (pintype "passive"))
      (node (ref "C9") (pin "1") (pinfunction "1_1") (pintype "passive"))
      (node (ref "FB1") (pin "2") (pinfunction "2_2") (pintype "passive"))
      (node (ref "J2") (pin "4") (pinfunction "VCI_4") (pintype "passive"))
      (node (ref "L2") (pin "2") (pinfunction "2_2") (pintype "passive"))
      (node (ref "R13") (pin "2") (pinfunction "2_2") (pintype "passive"))
      (node (ref "R18") (pin "2") (pinfunction "2_2") (pintype "passive"))
      (node (ref "R3") (pin "2") (pinfunction "2_2") (pintype "passive"))
      (node (ref "R7") (pin "2") (pinfunction "2_2") (pintype "passive"))
      (node (ref "R8") (pin "2") (pinfunction "2_2") (pintype "passive"))
      (node (ref "TF1") (pin "4") (pinfunction "VDD_4") (pintype "passive"))
      (node (ref "U2") (pin "C5") (pinfunction "VDDIO5B_C5") (pintype "power_in"))
      (node (ref "U2") (pin "C7") (pinfunction "VDDIO4B_C7") (pintype "power_in"))
      (node (ref "U2") (pin "C8") (pinfunction "VDDIO3B_C8") (pintype "power_in"))
      (node (ref "U2") (pin "D10") (pinfunction "VDDIO2A_D10") (pintype "power_in"))
      (node (ref "U2") (pin "G10") (pinfunction "VDDIO1A_G10") (pintype "power_in"))
      (node (ref "U2") (pin "H10") (pinfunction "VDDIO0A_H10") (pintype "power_in"))
      (node (ref "U5") (pin "3") (pinfunction "VCC_3") (pintype "passive"))
      (node (ref "V1") (pin "3") (pinfunction "Vin_3") (pintype "passive"))
    )
    (net (code "87") (name "5V") (class "Default")
      (node (ref "C14") (pin "2") (pinfunction "2_2") (pintype "passive"))
      (node (ref "C18") (pin "2") (pinfunction "2_2") (pintype "passive"))
      (node (ref "C19") (pin "2") (pinfunction "2_2") (pintype "passive"))
      (node (ref "C22") (pin "2") (pinfunction "2_2") (pintype "passive"))
      (node (ref "EA1") (pin "10") (pinfunction "VIN1_10") (pintype "passive"))
      (node (ref "EA1") (pin "16") (pinfunction "VCC_16") (pintype "passive"))
      (node (ref "EA1") (pin "18") (pinfunction "EN3_18") (pintype "passive"))
      (node (ref "EA1") (pin "19") (pinfunction "VIN3_19") (pintype "passive"))
      (node (ref "EA1") (pin "7") (pinfunction "VIN2_7") (pintype "passive"))
      (node (ref "EA1") (pin "8") (pinfunction "EN2_8") (pintype "passive"))
      (node (ref "EA1") (pin "9") (pinfunction "EN1_9") (pintype "passive"))
      (node (ref "J1") (pin "A4") (pinfunction "VBUS_A4") (pintype "passive"))
      (node (ref "J1") (pin "A9") (pinfunction "VBUS_A9") (pintype "passive"))
      (node (ref "J1") (pin "B4") (pinfunction "VBUS_B4") (pintype "passive"))
      (node (ref "J1") (pin "B9") (pinfunction "VBUS_B9") (pintype "passive"))
      (node (ref "P1") (pin "5") (pinfunction "5_5") (pintype "passive"))
      (node (ref "R10") (pin "1") (pinfunction "1_1") (pintype "passive"))
      (node (ref "U4") (pin "7") (pinfunction "REGIN_7") (pintype "passive"))
      (node (ref "U4") (pin "8") (pinfunction "VBUS_8") (pintype "power_in"))
    )
    (net (code "88") (name "AGND") (class "Default")
      (node (ref "C39") (pin "1") (pinfunction "1_1") (pintype "passive"))
      (node (ref "C40") (pin "1") (pinfunction "1_1") (pintype "passive"))
      (node (ref "C41") (pin "1") (pinfunction "1_1") (pintype "passive"))
      (node (ref "FB2") (pin "1") (pinfunction "1_1") (pintype "passive"))
      (node (ref "FPC1") (pin "23") (pinfunction "23_23") (pintype "passive"))
      (node (ref "V2") (pin "1") (pinfunction "GND_1") (pintype "passive"))
    )
    (net (code "89") (name "GND") (class "Default")
      (node (ref "BlueTooth") (pin "24") (pinfunction "GND_24") (pintype "passive"))
      (node (ref "C10") (pin "1") (pinfunction "1_1") (pintype "passive"))
      (node (ref "C11") (pin "2") (pinfunction "2_2") (pintype "passive"))
      (node (ref "C12") (pin "2") (pinfunction "2_2") (pintype "passive"))
      (node (ref "C13") (pin "2") (pinfunction "2_2") (pintype "passive"))
      (node (ref "C14") (pin "1") (pinfunction "1_1") (pintype "passive"))
      (node (ref "C15") (pin "2") (pinfunction "2_2") (pintype "passive"))
      (node (ref "C17") (pin "2") (pinfunction "2_2") (pintype "passive"))
      (node (ref "C18") (pin "1") (pinfunction "1_1") (pintype "passive"))
      (node (ref "C19") (pin "1") (pinfunction "1_1") (pintype "passive"))
      (node (ref "C2") (pin "1") (pinfunction "1_1") (pintype "passive"))
      (node (ref "C20") (pin "2") (pinfunction "2_2") (pintype "passive"))
      (node (ref "C22") (pin "1") (pinfunction "1_1") (pintype "passive"))
      (node (ref "C23") (pin "2") (pinfunction "2_2") (pintype "passive"))
      (node (ref "C24") (pin "2") (pinfunction "2_2") (pintype "passive"))
      (node (ref "C26") (pin "1") (pinfunction "1_1") (pintype "passive"))
      (node (ref "C27") (pin "1") (pinfunction "1_1") (pintype "passive"))
      (node (ref "C28") (pin "1") (pinfunction "1_1") (pintype "passive"))
      (node (ref "C29") (pin "1") (pinfunction "1_1") (pintype "passive"))
      (node (ref "C30") (pin "1") (pinfunction "1_1") (pintype "passive"))
      (node (ref "C31") (pin "1") (pinfunction "1_1") (pintype "passive"))
      (node (ref "C32") (pin "1") (pinfunction "1_1") (pintype "passive"))
      (node (ref "C33") (pin "1") (pinfunction "1_1") (pintype "passive"))
      (node (ref "C34") (pin "1") (pinfunction "1_1") (pintype "passive"))
      (node (ref "C35") (pin "1") (pinfunction "1_1") (pintype "passive"))
      (node (ref "C36") (pin "1") (pinfunction "1_1") (pintype "passive"))
      (node (ref "C37") (pin "1") (pinfunction "1_1") (pintype "passive"))
      (node (ref "C4") (pin "1") (pinfunction "1_1") (pintype "passive"))
      (node (ref "C42") (pin "1") (pinfunction "1_1") (pintype "passive"))
      (node (ref "C43") (pin "1") (pinfunction "1_1") (pintype "passive"))
      (node (ref "C44") (pin "1") (pinfunction "1_1") (pintype "passive"))
      (node (ref "C45") (pin "1") (pinfunction "1_1") (pintype "passive"))
      (node (ref "C46") (pin "1") (pinfunction "1_1") (pintype "passive"))
      (node (ref "C47") (pin "1") (pinfunction "1_1") (pintype "passive"))
      (node (ref "C48") (pin "1") (pinfunction "1_1") (pintype "passive"))
      (node (ref "C49") (pin "1") (pinfunction "1_1") (pintype "passive"))
      (node (ref "C50") (pin "1") (pinfunction "1_1") (pintype "passive"))
      (node (ref "C51") (pin "1") (pinfunction "1_1") (pintype "passive"))
      (node (ref "C52") (pin "1") (pinfunction "1_1") (pintype "passive"))
      (node (ref "C53") (pin "1") (pinfunction "1_1") (pintype "passive"))
      (node (ref "C54") (pin "1") (pinfunction "1_1") (pintype "passive"))
      (node (ref "C55") (pin "1") (pinfunction "1_1") (pintype "passive"))
      (node (ref "C7") (pin "1") (pinfunction "1_1") (pintype "passive"))
      (node (ref "C8") (pin "1") (pinfunction "1_1") (pintype "passive"))
      (node (ref "C9") (pin "2") (pinfunction "2_2") (pintype "passive"))
      (node (ref "D1") (pin "K") (pinfunction "K_K") (pintype "passive"))
      (node (ref "D3") (pin "K") (pinfunction "K_K") (pintype "passive"))
      (node (ref "EA1") (pin "1") (pinfunction "GND3_1") (pintype "passive"))
      (node (ref "EA1") (pin "12") (pinfunction "GND1_12") (pintype "passive"))
      (node (ref "EA1") (pin "13") (pinfunction "AGND_13") (pintype "passive"))
      (node (ref "EA1") (pin "15") (pinfunction "AGND_15") (pintype "passive"))
      (node (ref "EA1") (pin "17") (pinfunction "AGND_17") (pintype "passive"))
      (node (ref "EA1") (pin "21") (pinfunction "PAD_21") (pintype "passive"))
      (node (ref "EA1") (pin "4") (pinfunction "AGND_4") (pintype "passive"))
      (node (ref "EA1") (pin "5") (pinfunction "GND2_5") (pintype "passive"))
      (node (ref "FB2") (pin "2") (pinfunction "2_2") (pintype "passive"))
      (node (ref "FPC1") (pin "10") (pinfunction "10_10") (pintype "passive"))
      (node (ref "J1") (pin "A1") (pinfunction "GND_A1") (pintype "passive"))
      (node (ref "J1") (pin "A12") (pinfunction "GND_A12") (pintype "passive"))
      (node (ref "J1") (pin "B1") (pinfunction "GND_B1") (pintype "passive"))
      (node (ref "J1") (pin "B12") (pinfunction "GND_B12") (pintype "passive"))
      (node (ref "J2") (pin "1") (pinfunction "LEDK_1") (pintype "passive"))
      (node (ref "J2") (pin "20") (pinfunction "GND_20") (pintype "passive"))
      (node (ref "J2") (pin "25") (pinfunction "pad_25") (pintype "passive"))
      (node (ref "J2") (pin "26") (pinfunction "pad_26") (pintype "passive"))
      (node (ref "J2") (pin "3") (pinfunction "GND_3") (pintype "passive"))
      (node (ref "P1") (pin "1") (pinfunction "1_1") (pintype "passive"))
      (node (ref "R12") (pin "2") (pinfunction "2_2") (pintype "passive"))
      (node (ref "R15") (pin "2") (pinfunction "2_2") (pintype "passive"))
      (node (ref "R17") (pin "2") (pinfunction "2_2") (pintype "passive"))
      (node (ref "R20") (pin "1") (pinfunction "1_1") (pintype "passive"))
      (node (ref "S1") (pin "2") (pinfunction "2_2") (pintype "passive"))
      (node (ref "S2") (pin "2") (pinfunction "2_2") (pintype "passive"))
      (node (ref "TF1") (pin "10") (pinfunction "PAD1_10") (pintype "passive"))
      (node (ref "TF1") (pin "11") (pinfunction "PAD2_11") (pintype "passive"))
      (node (ref "TF1") (pin "12") (pinfunction "PAD3_12") (pintype "passive"))
      (node (ref "TF1") (pin "6") (pinfunction "GND_6") (pintype "passive"))
      (node (ref "TF1") (pin "9") (pinfunction "PAD4_9") (pintype "passive"))
      (node (ref "U2") (pin "C10") (pinfunction "VSS_C10") (pintype "power_in"))
      (node (ref "U2") (pin "C3") (pinfunction "VSS_C3") (pintype "power_in"))
      (node (ref "U2") (pin "C4") (pinfunction "VSS_C4") (pintype "power_in"))
      (node (ref "U2") (pin "C6") (pinfunction "VSS_C6") (pintype "power_in"))
      (node (ref "U2") (pin "C9") (pinfunction "VSS_C9") (pintype "power_in"))
      (node (ref "U2") (pin "D5") (pinfunction "VSS_D5") (pintype "power_in"))
      (node (ref "U2") (pin "D7") (pinfunction "VSS_D7") (pintype "power_in"))
      (node (ref "U2") (pin "D8") (pinfunction "VSS_D8") (pintype "power_in"))
      (node (ref "U2") (pin "E10") (pinfunction "VSS_E10") (pintype "power_in"))
      (node (ref "U2") (pin "E3") (pinfunction "VSS_E3") (pintype "power_in"))
      (node (ref "U2") (pin "E4") (pinfunction "VSS_E4") (pintype "power_in"))
      (node (ref "U2") (pin "E5") (pinfunction "VSS_E5") (pintype "power_in"))
      (node (ref "U2") (pin "E6") (pinfunction "VSS_E6") (pintype "power_in"))
      (node (ref "U2") (pin "E8") (pinfunction "VSS_E8") (pintype "power_in"))
      (node (ref "U2") (pin "F10") (pinfunction "VSS_F10") (pintype "power_in"))
      (node (ref "U2") (pin "F5") (pinfunction "VSS_F5") (pintype "power_in"))
      (node (ref "U2") (pin "F7") (pinfunction "VSS_F7") (pintype "power_in"))
      (node (ref "U2") (pin "F8") (pinfunction "VSS_F8") (pintype "power_in"))
      (node (ref "U2") (pin "F9") (pinfunction "VSS_F9") (pintype "power_in"))
      (node (ref "U2") (pin "G3") (pinfunction "VSS_G3") (pintype "power_in"))
      (node (ref "U2") (pin "G4") (pinfunction "VSS_G4") (pintype "power_in"))
      (node (ref "U2") (pin "G5") (pinfunction "VSS_G5") (pintype "power_in"))
      (node (ref "U2") (pin "G6") (pinfunction "VSS_G6") (pintype "power_in"))
      (node (ref "U2") (pin "G8") (pinfunction "VSS_G8") (pintype "power_in"))
      (node (ref "U2") (pin "H2") (pinfunction "VSS_H2") (pintype "power_in"))
      (node (ref "U2") (pin "H5") (pinfunction "VSS_H5") (pintype "power_in"))
      (node (ref "U2") (pin "H7") (pinfunction "VSS_H7") (pintype "power_in"))
      (node (ref "U2") (pin "H8") (pinfunction "VSS_H8") (pintype "power_in"))
      (node (ref "U2") (pin "H9") (pinfunction "VSS_H9") (pintype "power_in"))
      (node (ref "U2") (pin "J10") (pinfunction "VSS_J10") (pintype "power_in"))
      (node (ref "U2") (pin "J2") (pinfunction "VSS_J2") (pintype "power_in"))
      (node (ref "U2") (pin "J4") (pinfunction "VSS_J4") (pintype "power_in"))
      (node (ref "U2") (pin "J6") (pinfunction "VSS_J6") (pintype "power_in"))
      (node (ref "U2") (pin "J8") (pinfunction "VSS_J8") (pintype "power_in"))
      (node (ref "U2") (pin "K10") (pinfunction "VSS_K10") (pintype "power_in"))
      (node (ref "U2") (pin "K2") (pinfunction "VSS_K2") (pintype "power_in"))
      (node (ref "U2") (pin "K3") (pinfunction "VSS_K3") (pintype "power_in"))
      (node (ref "U2") (pin "K5") (pinfunction "VSS_K5") (pintype "power_in"))
      (node (ref "U2") (pin "K7") (pinfunction "VSS_K7") (pintype "power_in"))
      (node (ref "U2") (pin "K9") (pinfunction "VSS_K9") (pintype "power_in"))
      (node (ref "U2") (pin "L2") (pinfunction "VSS_L2") (pintype "power_in"))
      (node (ref "U4") (pin "2") (pinfunction "GND_2") (pintype "power_in"))
      (node (ref "U4") (pin "25") (pinfunction "GND_25") (pintype "power_in"))
      (node (ref "U5") (pin "1") (pinfunction "GND_1") (pintype "passive"))
      (node (ref "U6") (pin "4") (pinfunction "GND_4") (pintype "passive"))
      (node (ref "V1") (pin "1") (pinfunction "GND_1") (pintype "passive"))
      (node (ref "X1") (pin "2") (pinfunction "GND_2") (pintype "passive"))
      (node (ref "X1") (pin "4") (pinfunction "GND_4") (pintype "passive"))
    )
    (net (code "90") (name "Net-(BlueTooth-PWRC)") (class "Default")
      (node (ref "BlueTooth") (pin "22") (pinfunction "PWRC_22") (pintype "passive"))
      (node (ref "Rpwr") (pin "1") (pinfunction "1_1") (pintype "passive"))
    )
    (net (code "91") (name "Net-(BlueTooth-STAT)") (class "Default")
      (node (ref "BlueTooth") (pin "6") (pinfunction "STAT_6") (pintype "passive"))
      (node (ref "Rstat") (pin "1") (pinfunction "1_1") (pintype "passive"))
    )
    (net (code "92") (name "Net-(D1-PadA)") (class "Default")
      (node (ref "D1") (pin "A") (pinfunction "A_A") (pintype "passive"))
      (node (ref "R10") (pin "2") (pinfunction "2_2") (pintype "passive"))
    )
    (net (code "93") (name "Net-(EA1-FB1)") (class "Default")
      (node (ref "C16") (pin "2") (pinfunction "2_2") (pintype "passive"))
      (node (ref "EA1") (pin "14") (pinfunction "FB1_14") (pintype "passive"))
      (node (ref "R11") (pin "1") (pinfunction "1_1") (pintype "passive"))
      (node (ref "R12") (pin "1") (pinfunction "1_1") (pintype "passive"))
    )
    (net (code "94") (name "Net-(EA1-FB2)") (class "Default")
      (node (ref "C21") (pin "2") (pinfunction "2_2") (pintype "passive"))
      (node (ref "EA1") (pin "3") (pinfunction "FB2_3") (pintype "passive"))
      (node (ref "R13") (pin "1") (pinfunction "1_1") (pintype "passive"))
      (node (ref "R15") (pin "1") (pinfunction "1_1") (pintype "passive"))
    )
    (net (code "95") (name "Net-(EA1-FB3)") (class "Default")
      (node (ref "C25") (pin "2") (pinfunction "2_2") (pintype "passive"))
      (node (ref "EA1") (pin "2") (pinfunction "FB3_2") (pintype "passive"))
      (node (ref "R16") (pin "1") (pinfunction "1_1") (pintype "passive"))
      (node (ref "R17") (pin "1") (pinfunction "1_1") (pintype "passive"))
    )
    (net (code "96") (name "Net-(EA1-SW1)") (class "Default")
      (node (ref "EA1") (pin "11") (pinfunction "SW1_11") (pintype "passive"))
      (node (ref "L1") (pin "1") (pinfunction "1_1") (pintype "passive"))
    )
    (net (code "97") (name "Net-(EA1-SW2)") (class "Default")
      (node (ref "EA1") (pin "6") (pinfunction "SW2_6") (pintype "passive"))
      (node (ref "L2") (pin "1") (pinfunction "1_1") (pintype "passive"))
    )
    (net (code "98") (name "Net-(EA1-SW3)") (class "Default")
      (node (ref "EA1") (pin "20") (pinfunction "SW3_20") (pintype "passive"))
      (node (ref "L3") (pin "1") (pinfunction "1_1") (pintype "passive"))
    )
    (net (code "99") (name "Net-(J2-LEDA)") (class "Default")
      (node (ref "J2") (pin "2") (pinfunction "LEDA_2") (pintype "passive"))
      (node (ref "R18") (pin "1") (pinfunction "1_1") (pintype "passive"))
    )
    (net (code "100") (name "Net-(U2B-CLK)") (class "Default")
      (node (ref "U2") (pin "L3") (pinfunction "OSC_CLK_L3") (pintype "passive"))
      (node (ref "U2") (pin "M2") (pinfunction "CLK_M2") (pintype "passive"))
    )
    (net (code "101") (name "Net-(U2B-XTAL_IN)") (class "Default")
      (node (ref "C7") (pin "2") (pinfunction "2_2") (pintype "passive"))
      (node (ref "R9") (pin "2") (pinfunction "2_2") (pintype "passive"))
      (node (ref "U2") (pin "M4") (pinfunction "XTAL_IN_M4") (pintype "passive"))
      (node (ref "X1") (pin "1") (pinfunction "XI_1") (pintype "passive"))
    )
    (net (code "102") (name "Net-(U2B-XTAL_OUT)") (class "Default")
      (node (ref "C8") (pin "2") (pinfunction "2_2") (pintype "passive"))
      (node (ref "R9") (pin "1") (pinfunction "1_1") (pintype "passive"))
      (node (ref "U2") (pin "M3") (pinfunction "XTAL_OUT_M3") (pintype "passive"))
      (node (ref "X1") (pin "3") (pinfunction "XO_3") (pintype "passive"))
    )
    (net (code "103") (name "Net-(U2C-VDDOTP)") (class "Default")
      (node (ref "C23") (pin "1") (pinfunction "1_1") (pintype "passive"))
      (node (ref "R14") (pin "1") (pinfunction "1_1") (pintype "passive"))
      (node (ref "U2") (pin "J3") (pinfunction "VDDOTP_J3") (pintype "power_in"))
    )
    (net (code "104") (name "Net-(U2C-VDDPLL)") (class "Default")
      (node (ref "C38") (pin "2") (pinfunction "2_2") (pintype "passive"))
      (node (ref "C56") (pin "2") (pinfunction "2_2") (pintype "passive"))
      (node (ref "R19") (pin "1") (pinfunction "1_1") (pintype "passive"))
      (node (ref "U2") (pin "L4") (pinfunction "VDDPLL_L4") (pintype "power_in"))
    )
    (net (code "105") (name "Net-(U2C-VSSPLL)") (class "Default")
      (node (ref "C38") (pin "1") (pinfunction "1_1") (pintype "passive"))
      (node (ref "C56") (pin "1") (pinfunction "1_1") (pintype "passive"))
      (node (ref "R20") (pin "2") (pinfunction "2_2") (pintype "passive"))
      (node (ref "U2") (pin "K4") (pinfunction "VSSPLL_K4") (pintype "power_in"))
    )
    (net (code "106") (name "Net-(U4-VDD)") (class "Default")
      (node (ref "C2") (pin "2") (pinfunction "2_2") (pintype "passive"))
      (node (ref "R1") (pin "2") (pinfunction "2_2") (pintype "passive"))
      (node (ref "U4") (pin "5") (pinfunction "VIO_5") (pintype "passive"))
      (node (ref "U4") (pin "6") (pinfunction "VDD_6") (pintype "passive"))
    )
    (net (code "107") (name "Net-(U4-~{RS}T)") (class "Default")
      (node (ref "R1") (pin "1") (pinfunction "1_1") (pintype "passive"))
      (node (ref "U4") (pin "9") (pinfunction "~{RS}T_9") (pintype "passive"))
    )
    (net (code "108") (name "Net-(V2-Vin)") (class "Default")
      (node (ref "C39") (pin "2") (pinfunction "2_2") (pintype "passive"))
      (node (ref "FB1") (pin "1") (pinfunction "1_1") (pintype "passive"))
      (node (ref "V2") (pin "3") (pinfunction "Vin_3") (pintype "passive"))
    )
    (net (code "109") (name "unconnected-(FPC1-Pad1)") (class "Default")
      (node (ref "FPC1") (pin "1") (pinfunction "1_1") (pintype "passive+no_connect"))
    )
    (net (code "110") (name "unconnected-(FPC1-Pad2)") (class "Default")
      (node (ref "FPC1") (pin "2") (pinfunction "2_2") (pintype "passive+no_connect"))
    )
    (net (code "111") (name "unconnected-(FPC1-Pad24)") (class "Default")
      (node (ref "FPC1") (pin "24") (pinfunction "24_24") (pintype "passive+no_connect"))
    )
    (net (code "112") (name "unconnected-(J1-CC1-PadA5)") (class "Default")
      (node (ref "J1") (pin "A5") (pinfunction "CC1_A5") (pintype "passive"))
    )
    (net (code "113") (name "unconnected-(J1-CC2-PadB5)") (class "Default")
      (node (ref "J1") (pin "B5") (pinfunction "CC2_B5") (pintype "passive"))
    )
    (net (code "114") (name "unconnected-(J1-SBU1-PadA8)") (class "Default")
      (node (ref "J1") (pin "A8") (pinfunction "SBU1_A8") (pintype "passive"))
    )
    (net (code "115") (name "unconnected-(J1-SBU2-PadB8)") (class "Default")
      (node (ref "J1") (pin "B8") (pinfunction "SBU2_B8") (pintype "passive"))
    )
    (net (code "116") (name "unconnected-(J1-pad-Pad0)") (class "Default")
      (node (ref "J1") (pin "0") (pinfunction "pad_0") (pintype "passive+no_connect"))
    )
    (net (code "117") (name "unconnected-(J1-pad-Pad0)_1") (class "Default")
      (node (ref "J1") (pin "0") (pinfunction "pad_0") (pintype "passive+no_connect"))
    )
    (net (code "118") (name "unconnected-(J1-pad-Pad0)_2") (class "Default")
      (node (ref "J1") (pin "0") (pinfunction "pad_0") (pintype "passive+no_connect"))
    )
    (net (code "119") (name "unconnected-(J1-pad-Pad0)_3") (class "Default")
      (node (ref "J1") (pin "0") (pinfunction "pad_0") (pintype "passive+no_connect"))
    )
    (net (code "120") (name "unconnected-(J2-NC-Pad6)") (class "Default")
      (node (ref "J2") (pin "6") (pinfunction "NC_6") (pintype "passive+no_connect"))
    )
    (net (code "121") (name "unconnected-(J2-NC-Pad21)") (class "Default")
      (node (ref "J2") (pin "21") (pinfunction "NC_21") (pintype "passive+no_connect"))
    )
    (net (code "122") (name "unconnected-(J2-NC-Pad22)") (class "Default")
      (node (ref "J2") (pin "22") (pinfunction "NC_22") (pintype "passive+no_connect"))
    )
    (net (code "123") (name "unconnected-(J2-NC-Pad23)") (class "Default")
      (node (ref "J2") (pin "23") (pinfunction "NC_23") (pintype "passive+no_connect"))
    )
    (net (code "124") (name "unconnected-(J2-NC-Pad24)") (class "Default")
      (node (ref "J2") (pin "24") (pinfunction "NC_24") (pintype "passive+no_connect"))
    )
    (net (code "125") (name "unconnected-(TF1-DAT1-Pad8)") (class "Default")
      (node (ref "TF1") (pin "8") (pinfunction "DAT1_8") (pintype "passive+no_connect"))
    )
    (net (code "126") (name "unconnected-(TF1-DAT2-Pad1)") (class "Default")
      (node (ref "TF1") (pin "1") (pinfunction "DAT2_1") (pintype "passive+no_connect"))
    )
    (net (code "127") (name "unconnected-(U2A-IO_11-PadE12)") (class "Default")
      (node (ref "U2") (pin "E12") (pinfunction "IO_11_E12") (pintype "passive"))
    )
    (net (code "128") (name "unconnected-(U2A-IO_15-PadC12)") (class "Default")
      (node (ref "U2") (pin "C12") (pinfunction "IO_15_C12") (pintype "passive"))
    )
    (net (code "129") (name "unconnected-(U2A-IO_17-PadA12)") (class "Default")
      (node (ref "U2") (pin "A12") (pinfunction "IO_17_A12") (pintype "passive"))
    )
    (net (code "130") (name "unconnected-(U4-CTS-Pad18)") (class "Default")
      (node (ref "U4") (pin "18") (pinfunction "CTS_18") (pintype "passive+no_connect"))
    )
    (net (code "131") (name "unconnected-(U4-DCD-Pad24)") (class "Default")
      (node (ref "U4") (pin "24") (pinfunction "DCD_24") (pintype "passive+no_connect"))
    )
    (net (code "132") (name "unconnected-(U4-DSR-Pad22)") (class "Default")
      (node (ref "U4") (pin "22") (pinfunction "DSR_22") (pintype "passive+no_connect"))
    )
    (net (code "133") (name "unconnected-(U4-GPIO.2-Pad12)") (class "Default")
      (node (ref "U4") (pin "12") (pinfunction "GPIO.2_12") (pintype "passive"))
    )
    (net (code "134") (name "unconnected-(U4-GPIO.3-Pad11)") (class "Default")
      (node (ref "U4") (pin "11") (pinfunction "GPIO.3_11") (pintype "passive"))
    )
    (net (code "135") (name "unconnected-(U4-NC-Pad10)") (class "Default")
      (node (ref "U4") (pin "10") (pinfunction "NC_10") (pintype "passive"))
    )
    (net (code "136") (name "unconnected-(U4-RI-Pad1)") (class "Default")
      (node (ref "U4") (pin "1") (pinfunction "RI_1") (pintype "passive+no_connect"))
    )
    (net (code "137") (name "unconnected-(U4-SUSPEND-Pad17)") (class "Default")
      (node (ref "U4") (pin "17") (pinfunction "SUSPEND_17") (pintype "passive+no_connect"))
    )
    (net (code "138") (name "unconnected-(U4-VPP-Pad16)") (class "Default")
      (node (ref "U4") (pin "16") (pinfunction "VPP_16") (pintype "passive"))
    )
    (net (code "139") (name "unconnected-(U4-~{SUSPEND}-Pad15)") (class "Default")
      (node (ref "U4") (pin "15") (pinfunction "~{SUSPEND}_15") (pintype "passive+no_connect"))
    )
  )
)
